# transmitter.net
KiCad netlist of a schematic drawn in EAGLE
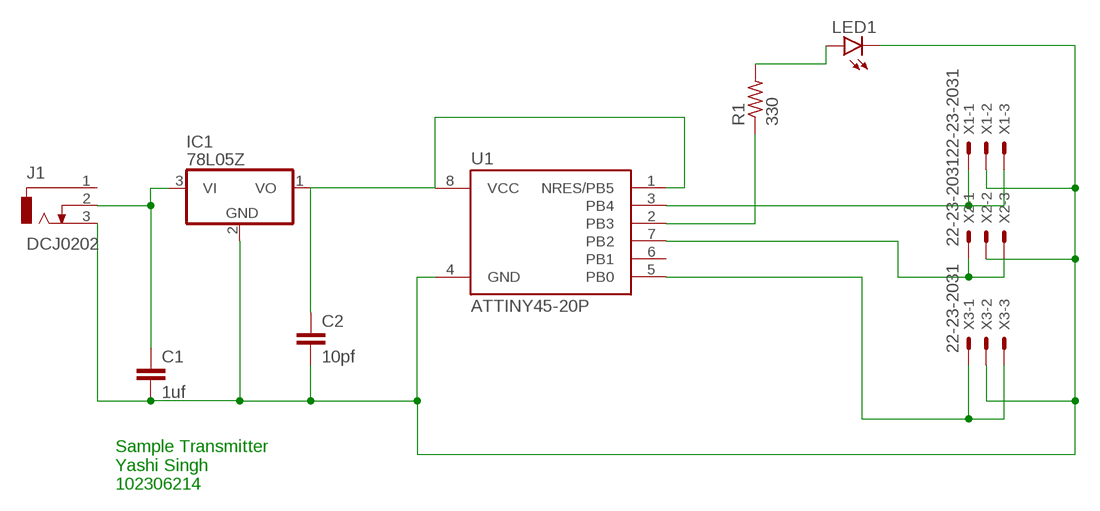
[diagram p0: schematic, sheet 1]

(export (version "E")
  (design (tool "Eeschema 10.0.6"))
  (components
    (comp (ref "C1")
      (value "1uf")
      (footprint "eagle-import:C2.5-2")
      (libsource (lib "eagle-import") (part "C2.5/2"))
    )
    (comp (ref "C2")
      (value "10pf")
      (footprint "eagle-import:C2.5-2")
      (libsource (lib "eagle-import") (part "C2.5/2"))
    )
    (comp (ref "IC1")
      (value "78L05Z")
      (footprint "eagle-import:TO92")
      (libsource (lib "eagle-import") (part "78ZL05"))
    )
    (comp (ref "J1")
      (value "DCJ0202")
      (footprint "eagle-import:DCJ0202")
      (libsource (lib "eagle-import") (part "DCJ0202"))
    )
    (comp (ref "LED1")
      (value "LED3MM")
      (footprint "eagle-import:LED3MM")
      (libsource (lib "eagle-import") (part "LED3MM"))
    )
    (comp (ref "R1")
      (value "330")
      (footprint "eagle-import:0207_10")
      (libsource (lib "eagle-import") (part "R-US_0207/10"))
    )
    (comp (ref "U1")
      (value "ATTINY45-20P")
      (footprint "eagle-import:PDIP08_300MIL")
      (libsource (lib "eagle-import") (part "ATTINY45P-20"))
    )
    (comp (ref "X1")
      (value "22-23-2031")
      (footprint "eagle-import:22-23-2031")
      (fields (field (name "MF") "MOLEX"))
      (libsource (lib "eagle-import") (part "22-23-2031"))
    )
    (comp (ref "X2")
      (value "22-23-2031")
      (footprint "eagle-import:22-23-2031")
      (fields (field (name "MF") "MOLEX"))
      (libsource (lib "eagle-import") (part "22-23-2031"))
    )
    (comp (ref "X3")
      (value "22-23-2031")
      (footprint "eagle-import:22-23-2031")
      (fields (field (name "MF") "MOLEX"))
      (libsource (lib "eagle-import") (part "22-23-2031"))
    )
  )
  (nets
    (net (code "1") (name "Net-(IC1-GND)") (class "Default")
      (node (ref "C1") (pin "2") (pinfunction "2_2") (pintype "passive"))
      (node (ref "C2") (pin "2") (pinfunction "2_2") (pintype "passive"))
      (node (ref "IC1") (pin "2") (pinfunction "GND_2") (pintype "passive"))
      (node (ref "J1") (pin "3") (pinfunction "3_3") (pintype "passive"))
      (node (ref "LED1") (pin "K") (pinfunction "C_K") (pintype "passive"))
      (node (ref "U1") (pin "4") (pinfunction "GND_4") (pintype "power_in"))
      (node (ref "X1") (pin "2") (pinfunction "S_2") (pintype "passive"))
      (node (ref "X2") (pin "2") (pinfunction "S_2") (pintype "passive"))
      (node (ref "X3") (pin "2") (pinfunction "S_2") (pintype "passive"))
    )
    (net (code "2") (name "Net-(IC1-VI)") (class "Default")
      (node (ref "C1") (pin "1") (pinfunction "1_1") (pintype "passive"))
      (node (ref "IC1") (pin "3") (pinfunction "VI_3") (pintype "input"))
      (node (ref "J1") (pin "2") (pinfunction "2_2") (pintype "passive"))
    )
    (net (code "3") (name "Net-(IC1-VO)") (class "Default")
      (node (ref "C2") (pin "1") (pinfunction "1_1") (pintype "passive"))
      (node (ref "IC1") (pin "1") (pinfunction "VO_1") (pintype "passive"))
      (node (ref "U1") (pin "1") (pinfunction "NRES/PB5_1") (pintype "bidirectional"))
      (node (ref "U1") (pin "8") (pinfunction "VCC_8") (pintype "power_in"))
    )
    (net (code "4") (name "Net-(LED1-PadA)") (class "Default")
      (node (ref "LED1") (pin "A") (pinfunction "A_A") (pintype "passive"))
      (node (ref "R1") (pin "2") (pinfunction "2_2") (pintype "passive"))
    )
    (net (code "5") (name "Net-(U1-PB0)") (class "Default")
      (node (ref "U1") (pin "5") (pinfunction "PB0_5") (pintype "bidirectional"))
      (node (ref "X3") (pin "1") (pinfunction "S_1") (pintype "passive"))
      (node (ref "X3") (pin "3") (pinfunction "S_3") (pintype "passive"))
    )
    (net (code "6") (name "Net-(U1-PB2)") (class "Default")
      (node (ref "U1") (pin "7") (pinfunction "PB2_7") (pintype "bidirectional"))
      (node (ref "X2") (pin "1") (pinfunction "S_1") (pintype "passive"))
      (node (ref "X2") (pin "3") (pinfunction "S_3") (pintype "passive"))
    )
    (net (code "7") (name "Net-(U1-PB3)") (class "Default")
      (node (ref "R1") (pin "1") (pinfunction "1_1") (pintype "passive"))
      (node (ref "U1") (pin "2") (pinfunction "PB3_2") (pintype "bidirectional"))
    )
    (net (code "8") (name "Net-(U1-PB4)") (class "Default")
      (node (ref "U1") (pin "3") (pinfunction "PB4_3") (pintype "bidirectional"))
      (node (ref "X1") (pin "1") (pinfunction "S_1") (pintype "passive"))
      (node (ref "X1") (pin "3") (pinfunction "S_3") (pintype "passive"))
    )
    (net (code "9") (name "unconnected-(J1-Pad1)") (class "Default")
      (node (ref "J1") (pin "1") (pinfunction "1_1") (pintype "passive"))
    )
    (net (code "10") (name "unconnected-(U1-PB1-Pad6)") (class "Default")
      (node (ref "U1") (pin "6") (pinfunction "PB1_6") (pintype "bidirectional"))
    )
  )
)
